# sche_DPN_ControlLed.net
KiCad netlist of a schematic drawn in Altium Designer
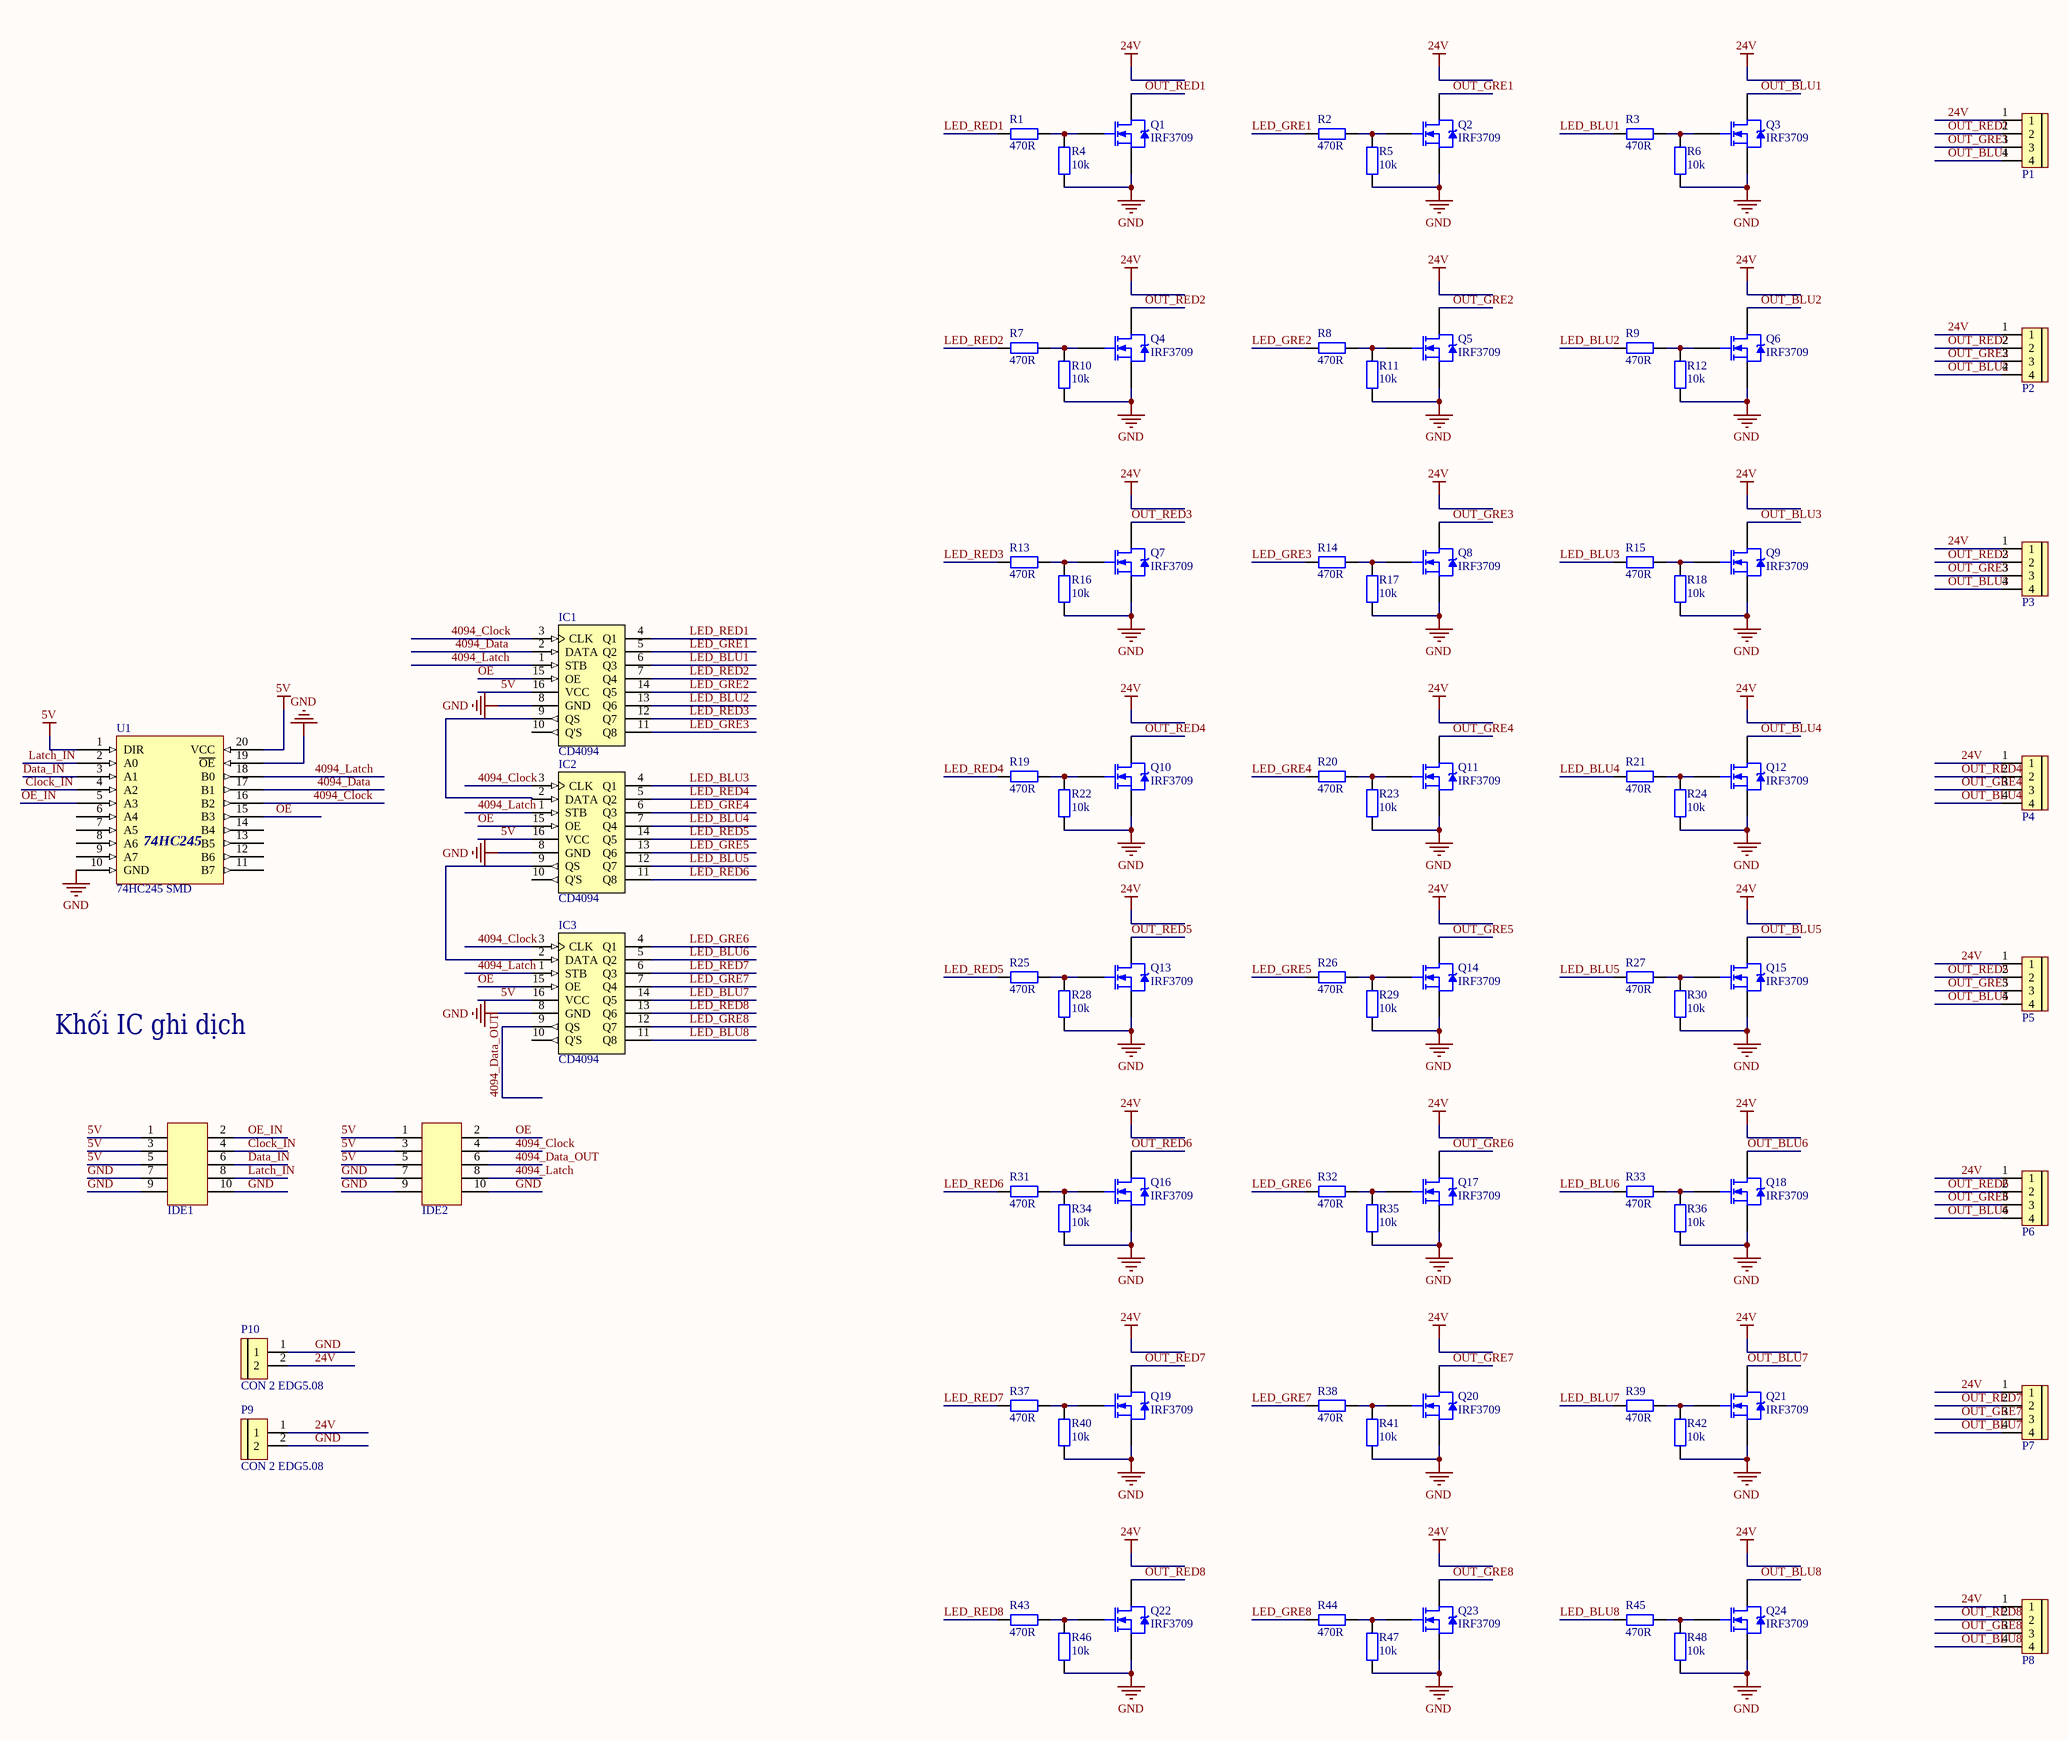
[diagram p0: sche_DPN_ControlLed.SchDoc]

(export (version "E")
  (design (tool "Eeschema 10.0.6"))
  (components
    (comp (ref "IC1")
      (value "CD4094")
      (footprint "CD4094")
      (description "Dán")
      (libsource (lib "IC") (part "CD4094 SMD"))
    )
    (comp (ref "IC2")
      (value "CD4094")
      (footprint "CD4094")
      (description "Dán")
      (libsource (lib "IC") (part "CD4094 SMD"))
    )
    (comp (ref "IC3")
      (value "CD4094")
      (footprint "CD4094")
      (description "Dán")
      (libsource (lib "IC") (part "CD4094 SMD"))
    )
    (comp (ref "IDE1")
      (value "IDE10")
      (footprint "IDE10_Cong")
      (libsource (lib "Component") (part "IDE 10 DT"))
    )
    (comp (ref "IDE2")
      (value "IDE10")
      (footprint "IDE10_Cong")
      (libsource (lib "Component") (part "IDE 10 DT"))
    )
    (comp (ref "P1")
      (value "CON 4 EDG5.08")
      (footprint "CON 4 4EDG5.08")
      (description "Cắm")
      (libsource (lib "Connector") (part "CON 4 EDG5.08"))
    )
    (comp (ref "P2")
      (value "CON 4 EDG5.08")
      (footprint "CON 4 4EDG5.08")
      (description "Cắm")
      (libsource (lib "Connector") (part "CON 4 EDG5.08"))
    )
    (comp (ref "P3")
      (value "CON 4 EDG5.08")
      (footprint "CON 4 4EDG5.08")
      (description "Cắm")
      (libsource (lib "Connector") (part "CON 4 EDG5.08"))
    )
    (comp (ref "P4")
      (value "CON 4 EDG5.08")
      (footprint "CON 4 4EDG5.08")
      (description "Cắm")
      (libsource (lib "Connector") (part "CON 4 EDG5.08"))
    )
    (comp (ref "P5")
      (value "CON 4 EDG5.08")
      (footprint "CON 4 4EDG5.08")
      (description "Cắm")
      (libsource (lib "Connector") (part "CON 4 EDG5.08"))
    )
    (comp (ref "P6")
      (value "CON 4 EDG5.08")
      (footprint "CON 4 4EDG5.08")
      (description "Cắm")
      (libsource (lib "Connector") (part "CON 4 EDG5.08"))
    )
    (comp (ref "P7")
      (value "CON 4 EDG5.08")
      (footprint "CON 4 4EDG5.08")
      (description "Cắm")
      (libsource (lib "Connector") (part "CON 4 EDG5.08"))
    )
    (comp (ref "P8")
      (value "CON 4 EDG5.08")
      (footprint "CON 4 4EDG5.08")
      (description "Cắm")
      (libsource (lib "Connector") (part "CON 4 EDG5.08"))
    )
    (comp (ref "P9")
      (value "CON 2 EDG5.08")
      (footprint "CON 2 2EDG5.08")
      (description "Cắm")
      (libsource (lib "Connector") (part "CON 2 EDG5.08"))
    )
    (comp (ref "P10")
      (value "CON 2 EDG5.08")
      (footprint "CON 2 2EDG5.08")
      (description "Cắm")
      (libsource (lib "Connector") (part "CON 2 EDG5.08"))
    )
    (comp (ref "Q1")
      (value "IRF3709")
      (footprint "D2PAK")
      (description "N-Channel Power MOSFET")
      (libsource (lib "TranFet") (part "IRF3709S SMD"))
    )
    (comp (ref "Q2")
      (value "IRF3709")
      (footprint "D2PAK")
      (description "N-Channel Power MOSFET")
      (libsource (lib "TranFet") (part "IRF3709S SMD"))
    )
    (comp (ref "Q3")
      (value "IRF3709")
      (footprint "D2PAK")
      (description "N-Channel Power MOSFET")
      (libsource (lib "TranFet") (part "IRF3709S SMD"))
    )
    (comp (ref "Q4")
      (value "IRF3709")
      (footprint "D2PAK")
      (description "N-Channel Power MOSFET")
      (libsource (lib "TranFet") (part "IRF3709S SMD"))
    )
    (comp (ref "Q5")
      (value "IRF3709")
      (footprint "D2PAK")
      (description "N-Channel Power MOSFET")
      (libsource (lib "TranFet") (part "IRF3709S SMD"))
    )
    (comp (ref "Q6")
      (value "IRF3709")
      (footprint "D2PAK")
      (description "N-Channel Power MOSFET")
      (libsource (lib "TranFet") (part "IRF3709S SMD"))
    )
    (comp (ref "Q7")
      (value "IRF3709")
      (footprint "D2PAK")
      (description "N-Channel Power MOSFET")
      (libsource (lib "TranFet") (part "IRF3709S SMD"))
    )
    (comp (ref "Q8")
      (value "IRF3709")
      (footprint "D2PAK")
      (description "N-Channel Power MOSFET")
      (libsource (lib "TranFet") (part "IRF3709S SMD"))
    )
    (comp (ref "Q9")
      (value "IRF3709")
      (footprint "D2PAK")
      (description "N-Channel Power MOSFET")
      (libsource (lib "TranFet") (part "IRF3709S SMD"))
    )
    (comp (ref "Q10")
      (value "IRF3709")
      (footprint "D2PAK")
      (description "N-Channel Power MOSFET")
      (libsource (lib "TranFet") (part "IRF3709S SMD"))
    )
    (comp (ref "Q11")
      (value "IRF3709")
      (footprint "D2PAK")
      (description "N-Channel Power MOSFET")
      (libsource (lib "TranFet") (part "IRF3709S SMD"))
    )
    (comp (ref "Q12")
      (value "IRF3709")
      (footprint "D2PAK")
      (description "N-Channel Power MOSFET")
      (libsource (lib "TranFet") (part "IRF3709S SMD"))
    )
    (comp (ref "Q13")
      (value "IRF3709")
      (footprint "D2PAK")
      (description "N-Channel Power MOSFET")
      (libsource (lib "TranFet") (part "IRF3709S SMD"))
    )
    (comp (ref "Q14")
      (value "IRF3709")
      (footprint "D2PAK")
      (description "N-Channel Power MOSFET")
      (libsource (lib "TranFet") (part "IRF3709S SMD"))
    )
    (comp (ref "Q15")
      (value "IRF3709")
      (footprint "D2PAK")
      (description "N-Channel Power MOSFET")
      (libsource (lib "TranFet") (part "IRF3709S SMD"))
    )
    (comp (ref "Q16")
      (value "IRF3709")
      (footprint "D2PAK")
      (description "N-Channel Power MOSFET")
      (libsource (lib "TranFet") (part "IRF3709S SMD"))
    )
    (comp (ref "Q17")
      (value "IRF3709")
      (footprint "D2PAK")
      (description "N-Channel Power MOSFET")
      (libsource (lib "TranFet") (part "IRF3709S SMD"))
    )
    (comp (ref "Q18")
      (value "IRF3709")
      (footprint "D2PAK")
      (description "N-Channel Power MOSFET")
      (libsource (lib "TranFet") (part "IRF3709S SMD"))
    )
    (comp (ref "Q19")
      (value "IRF3709")
      (footprint "D2PAK")
      (description "N-Channel Power MOSFET")
      (libsource (lib "TranFet") (part "IRF3709S SMD"))
    )
    (comp (ref "Q20")
      (value "IRF3709")
      (footprint "D2PAK")
      (description "N-Channel Power MOSFET")
      (libsource (lib "TranFet") (part "IRF3709S SMD"))
    )
    (comp (ref "Q21")
      (value "IRF3709")
      (footprint "D2PAK")
      (description "N-Channel Power MOSFET")
      (libsource (lib "TranFet") (part "IRF3709S SMD"))
    )
    (comp (ref "Q22")
      (value "IRF3709")
      (footprint "D2PAK")
      (description "N-Channel Power MOSFET")
      (libsource (lib "TranFet") (part "IRF3709S SMD"))
    )
    (comp (ref "Q23")
      (value "IRF3709")
      (footprint "D2PAK")
      (description "N-Channel Power MOSFET")
      (libsource (lib "TranFet") (part "IRF3709S SMD"))
    )
    (comp (ref "Q24")
      (value "IRF3709")
      (footprint "D2PAK")
      (description "N-Channel Power MOSFET")
      (libsource (lib "TranFet") (part "IRF3709S SMD"))
    )
    (comp (ref "R1")
      (value "470R")
      (footprint "Tro SMD 0805")
      (description "Dán")
      (libsource (lib "Dien Tro") (part "Tro 0805 5% 470R"))
    )
    (comp (ref "R2")
      (value "470R")
      (footprint "Tro SMD 0805")
      (description "Dán")
      (libsource (lib "Dien Tro") (part "Tro 0805 5% 470R"))
    )
    (comp (ref "R3")
      (value "470R")
      (footprint "Tro SMD 0805")
      (description "Dán")
      (libsource (lib "Dien Tro") (part "Tro 0805 5% 470R"))
    )
    (comp (ref "R4")
      (value "10k")
      (footprint "tro smd 0805")
      (description "Dán")
      (libsource (lib "Dien Tro") (part "Tro 0805 5% 10k"))
    )
    (comp (ref "R5")
      (value "10k")
      (footprint "tro smd 0805")
      (description "Dán")
      (libsource (lib "Dien Tro") (part "Tro 0805 5% 10k"))
    )
    (comp (ref "R6")
      (value "10k")
      (footprint "tro smd 0805")
      (description "Dán")
      (libsource (lib "Dien Tro") (part "Tro 0805 5% 10k"))
    )
    (comp (ref "R7")
      (value "470R")
      (footprint "Tro SMD 0805")
      (description "Dán")
      (libsource (lib "Dien Tro") (part "Tro 0805 5% 470R"))
    )
    (comp (ref "R8")
      (value "470R")
      (footprint "Tro SMD 0805")
      (description "Dán")
      (libsource (lib "Dien Tro") (part "Tro 0805 5% 470R"))
    )
    (comp (ref "R9")
      (value "470R")
      (footprint "Tro SMD 0805")
      (description "Dán")
      (libsource (lib "Dien Tro") (part "Tro 0805 5% 470R"))
    )
    (comp (ref "R10")
      (value "10k")
      (footprint "tro smd 0805")
      (description "Dán")
      (libsource (lib "Dien Tro") (part "Tro 0805 5% 10k"))
    )
    (comp (ref "R11")
      (value "10k")
      (footprint "tro smd 0805")
      (description "Dán")
      (libsource (lib "Dien Tro") (part "Tro 0805 5% 10k"))
    )
    (comp (ref "R12")
      (value "10k")
      (footprint "tro smd 0805")
      (description "Dán")
      (libsource (lib "Dien Tro") (part "Tro 0805 5% 10k"))
    )
    (comp (ref "R13")
      (value "470R")
      (footprint "Tro SMD 0805")
      (description "Dán")
      (libsource (lib "Dien Tro") (part "Tro 0805 5% 470R"))
    )
    (comp (ref "R14")
      (value "470R")
      (footprint "Tro SMD 0805")
      (description "Dán")
      (libsource (lib "Dien Tro") (part "Tro 0805 5% 470R"))
    )
    (comp (ref "R15")
      (value "470R")
      (footprint "Tro SMD 0805")
      (description "Dán")
      (libsource (lib "Dien Tro") (part "Tro 0805 5% 470R"))
    )
    (comp (ref "R16")
      (value "10k")
      (footprint "tro smd 0805")
      (description "Dán")
      (libsource (lib "Dien Tro") (part "Tro 0805 5% 10k"))
    )
    (comp (ref "R17")
      (value "10k")
      (footprint "tro smd 0805")
      (description "Dán")
      (libsource (lib "Dien Tro") (part "Tro 0805 5% 10k"))
    )
    (comp (ref "R18")
      (value "10k")
      (footprint "tro smd 0805")
      (description "Dán")
      (libsource (lib "Dien Tro") (part "Tro 0805 5% 10k"))
    )
    (comp (ref "R19")
      (value "470R")
      (footprint "Tro SMD 0805")
      (description "Dán")
      (libsource (lib "Dien Tro") (part "Tro 0805 5% 470R"))
    )
    (comp (ref "R20")
      (value "470R")
      (footprint "Tro SMD 0805")
      (description "Dán")
      (libsource (lib "Dien Tro") (part "Tro 0805 5% 470R"))
    )
    (comp (ref "R21")
      (value "470R")
      (footprint "Tro SMD 0805")
      (description "Dán")
      (libsource (lib "Dien Tro") (part "Tro 0805 5% 470R"))
    )
    (comp (ref "R22")
      (value "10k")
      (footprint "tro smd 0805")
      (description "Dán")
      (libsource (lib "Dien Tro") (part "Tro 0805 5% 10k"))
    )
    (comp (ref "R23")
      (value "10k")
      (footprint "tro smd 0805")
      (description "Dán")
      (libsource (lib "Dien Tro") (part "Tro 0805 5% 10k"))
    )
    (comp (ref "R24")
      (value "10k")
      (footprint "tro smd 0805")
      (description "Dán")
      (libsource (lib "Dien Tro") (part "Tro 0805 5% 10k"))
    )
    (comp (ref "R25")
      (value "470R")
      (footprint "Tro SMD 0805")
      (description "Dán")
      (libsource (lib "Dien Tro") (part "Tro 0805 5% 470R"))
    )
    (comp (ref "R26")
      (value "470R")
      (footprint "Tro SMD 0805")
      (description "Dán")
      (libsource (lib "Dien Tro") (part "Tro 0805 5% 470R"))
    )
    (comp (ref "R27")
      (value "470R")
      (footprint "Tro SMD 0805")
      (description "Dán")
      (libsource (lib "Dien Tro") (part "Tro 0805 5% 470R"))
    )
    (comp (ref "R28")
      (value "10k")
      (footprint "tro smd 0805")
      (description "Dán")
      (libsource (lib "Dien Tro") (part "Tro 0805 5% 10k"))
    )
    (comp (ref "R29")
      (value "10k")
      (footprint "tro smd 0805")
      (description "Dán")
      (libsource (lib "Dien Tro") (part "Tro 0805 5% 10k"))
    )
    (comp (ref "R30")
      (value "10k")
      (footprint "tro smd 0805")
      (description "Dán")
      (libsource (lib "Dien Tro") (part "Tro 0805 5% 10k"))
    )
    (comp (ref "R31")
      (value "470R")
      (footprint "Tro SMD 0805")
      (description "Dán")
      (libsource (lib "Dien Tro") (part "Tro 0805 5% 470R"))
    )
    (comp (ref "R32")
      (value "470R")
      (footprint "Tro SMD 0805")
      (description "Dán")
      (libsource (lib "Dien Tro") (part "Tro 0805 5% 470R"))
    )
    (comp (ref "R33")
      (value "470R")
      (footprint "Tro SMD 0805")
      (description "Dán")
      (libsource (lib "Dien Tro") (part "Tro 0805 5% 470R"))
    )
    (comp (ref "R34")
      (value "10k")
      (footprint "tro smd 0805")
      (description "Dán")
      (libsource (lib "Dien Tro") (part "Tro 0805 5% 10k"))
    )
    (comp (ref "R35")
      (value "10k")
      (footprint "tro smd 0805")
      (description "Dán")
      (libsource (lib "Dien Tro") (part "Tro 0805 5% 10k"))
    )
    (comp (ref "R36")
      (value "10k")
      (footprint "tro smd 0805")
      (description "Dán")
      (libsource (lib "Dien Tro") (part "Tro 0805 5% 10k"))
    )
    (comp (ref "R37")
      (value "470R")
      (footprint "Tro SMD 0805")
      (description "Dán")
      (libsource (lib "Dien Tro") (part "Tro 0805 5% 470R"))
    )
    (comp (ref "R38")
      (value "470R")
      (footprint "Tro SMD 0805")
      (description "Dán")
      (libsource (lib "Dien Tro") (part "Tro 0805 5% 470R"))
    )
    (comp (ref "R39")
      (value "470R")
      (footprint "Tro SMD 0805")
      (description "Dán")
      (libsource (lib "Dien Tro") (part "Tro 0805 5% 470R"))
    )
    (comp (ref "R40")
      (value "10k")
      (footprint "tro smd 0805")
      (description "Dán")
      (libsource (lib "Dien Tro") (part "Tro 0805 5% 10k"))
    )
    (comp (ref "R41")
      (value "10k")
      (footprint "tro smd 0805")
      (description "Dán")
      (libsource (lib "Dien Tro") (part "Tro 0805 5% 10k"))
    )
    (comp (ref "R42")
      (value "10k")
      (footprint "tro smd 0805")
      (description "Dán")
      (libsource (lib "Dien Tro") (part "Tro 0805 5% 10k"))
    )
    (comp (ref "R43")
      (value "470R")
      (footprint "Tro SMD 0805")
      (description "Dán")
      (libsource (lib "Dien Tro") (part "Tro 0805 5% 470R"))
    )
    (comp (ref "R44")
      (value "470R")
      (footprint "Tro SMD 0805")
      (description "Dán")
      (libsource (lib "Dien Tro") (part "Tro 0805 5% 470R"))
    )
    (comp (ref "R45")
      (value "470R")
      (footprint "Tro SMD 0805")
      (description "Dán")
      (libsource (lib "Dien Tro") (part "Tro 0805 5% 470R"))
    )
    (comp (ref "R46")
      (value "10k")
      (footprint "tro smd 0805")
      (description "Dán")
      (libsource (lib "Dien Tro") (part "Tro 0805 5% 10k"))
    )
    (comp (ref "R47")
      (value "10k")
      (footprint "tro smd 0805")
      (description "Dán")
      (libsource (lib "Dien Tro") (part "Tro 0805 5% 10k"))
    )
    (comp (ref "R48")
      (value "10k")
      (footprint "tro smd 0805")
      (description "Dán")
      (libsource (lib "Dien Tro") (part "Tro 0805 5% 10k"))
    )
    (comp (ref "U1")
      (value "74HC245 SMD")
      (footprint "SOP 20")
      (description "Dán")
      (libsource (lib "IC") (part "74HC245 SMD"))
    )
  )
  (nets
    (net (code "1") (name "/4094_Clock") (class "Default")
      (node (ref "IC1") (pin "3") (pinfunction "CLK_3") (pintype "input"))
      (node (ref "IC2") (pin "3") (pinfunction "CLK_3") (pintype "input"))
      (node (ref "IC3") (pin "3") (pinfunction "CLK_3") (pintype "input"))
      (node (ref "IDE2") (pin "4") (pinfunction "4_4") (pintype "passive"))
      (node (ref "U1") (pin "16") (pinfunction "B2_16") (pintype "output"))
    )
    (net (code "2") (name "/4094_Data") (class "Default")
      (node (ref "IC1") (pin "2") (pinfunction "DATA_2") (pintype "input"))
      (node (ref "U1") (pin "17") (pinfunction "B1_17") (pintype "output"))
    )
    (net (code "3") (name "/4094_Data_OUT") (class "Default")
      (node (ref "IC3") (pin "9") (pinfunction "QS_9") (pintype "output"))
      (node (ref "IDE2") (pin "6") (pinfunction "6_6") (pintype "passive"))
    )
    (net (code "4") (name "/4094_Latch") (class "Default")
      (node (ref "IC1") (pin "1") (pinfunction "STB_1") (pintype "input"))
      (node (ref "IC2") (pin "1") (pinfunction "STB_1") (pintype "input"))
      (node (ref "IC3") (pin "1") (pinfunction "STB_1") (pintype "input"))
      (node (ref "IDE2") (pin "8") (pinfunction "8_8") (pintype "passive"))
      (node (ref "U1") (pin "18") (pinfunction "B0_18") (pintype "output"))
    )
    (net (code "5") (name "/Clock_IN") (class "Default")
      (node (ref "IDE1") (pin "4") (pinfunction "4_4") (pintype "passive"))
      (node (ref "U1") (pin "4") (pinfunction "A2_4") (pintype "input"))
    )
    (net (code "6") (name "/Data_IN") (class "Default")
      (node (ref "IDE1") (pin "6") (pinfunction "6_6") (pintype "passive"))
      (node (ref "U1") (pin "3") (pinfunction "A1_3") (pintype "input"))
    )
    (net (code "7") (name "/LED_BLU1") (class "Default")
      (node (ref "IC1") (pin "6") (pinfunction "Q3_6") (pintype "tri_state"))
      (node (ref "R3") (pin "1") (pinfunction "1_1") (pintype "passive"))
    )
    (net (code "8") (name "/LED_BLU2") (class "Default")
      (node (ref "IC1") (pin "13") (pinfunction "Q6_13") (pintype "tri_state"))
      (node (ref "R9") (pin "1") (pinfunction "1_1") (pintype "passive"))
    )
    (net (code "9") (name "/LED_BLU3") (class "Default")
      (node (ref "IC2") (pin "4") (pinfunction "Q1_4") (pintype "tri_state"))
      (node (ref "R15") (pin "1") (pinfunction "1_1") (pintype "passive"))
    )
    (net (code "10") (name "/LED_BLU4") (class "Default")
      (node (ref "IC2") (pin "7") (pinfunction "Q4_7") (pintype "tri_state"))
      (node (ref "R21") (pin "1") (pinfunction "1_1") (pintype "passive"))
    )
    (net (code "11") (name "/LED_BLU5") (class "Default")
      (node (ref "IC2") (pin "12") (pinfunction "Q7_12") (pintype "tri_state"))
      (node (ref "R27") (pin "1") (pinfunction "1_1") (pintype "passive"))
    )
    (net (code "12") (name "/LED_BLU6") (class "Default")
      (node (ref "IC3") (pin "5") (pinfunction "Q2_5") (pintype "tri_state"))
      (node (ref "R33") (pin "1") (pinfunction "1_1") (pintype "passive"))
    )
    (net (code "13") (name "/LED_BLU7") (class "Default")
      (node (ref "IC3") (pin "14") (pinfunction "Q5_14") (pintype "tri_state"))
      (node (ref "R39") (pin "1") (pinfunction "1_1") (pintype "passive"))
    )
    (net (code "14") (name "/LED_BLU8") (class "Default")
      (node (ref "IC3") (pin "11") (pinfunction "Q8_11") (pintype "tri_state"))
      (node (ref "R45") (pin "1") (pinfunction "1_1") (pintype "passive"))
    )
    (net (code "15") (name "/LED_GRE1") (class "Default")
      (node (ref "IC1") (pin "5") (pinfunction "Q2_5") (pintype "tri_state"))
      (node (ref "R2") (pin "1") (pinfunction "1_1") (pintype "passive"))
    )
    (net (code "16") (name "/LED_GRE2") (class "Default")
      (node (ref "IC1") (pin "14") (pinfunction "Q5_14") (pintype "tri_state"))
      (node (ref "R8") (pin "1") (pinfunction "1_1") (pintype "passive"))
    )
    (net (code "17") (name "/LED_GRE3") (class "Default")
      (node (ref "IC1") (pin "11") (pinfunction "Q8_11") (pintype "tri_state"))
      (node (ref "R14") (pin "1") (pinfunction "1_1") (pintype "passive"))
    )
    (net (code "18") (name "/LED_GRE4") (class "Default")
      (node (ref "IC2") (pin "6") (pinfunction "Q3_6") (pintype "tri_state"))
      (node (ref "R20") (pin "1") (pinfunction "1_1") (pintype "passive"))
    )
    (net (code "19") (name "/LED_GRE5") (class "Default")
      (node (ref "IC2") (pin "13") (pinfunction "Q6_13") (pintype "tri_state"))
      (node (ref "R26") (pin "1") (pinfunction "1_1") (pintype "passive"))
    )
    (net (code "20") (name "/LED_GRE6") (class "Default")
      (node (ref "IC3") (pin "4") (pinfunction "Q1_4") (pintype "tri_state"))
      (node (ref "R32") (pin "1") (pinfunction "1_1") (pintype "passive"))
    )
    (net (code "21") (name "/LED_GRE7") (class "Default")
      (node (ref "IC3") (pin "7") (pinfunction "Q4_7") (pintype "tri_state"))
      (node (ref "R38") (pin "1") (pinfunction "1_1") (pintype "passive"))
    )
    (net (code "22") (name "/LED_GRE8") (class "Default")
      (node (ref "IC3") (pin "12") (pinfunction "Q7_12") (pintype "tri_state"))
      (node (ref "R44") (pin "1") (pinfunction "1_1") (pintype "passive"))
    )
    (net (code "23") (name "/LED_RED1") (class "Default")
      (node (ref "IC1") (pin "4") (pinfunction "Q1_4") (pintype "tri_state"))
      (node (ref "R1") (pin "1") (pinfunction "1_1") (pintype "passive"))
    )
    (net (code "24") (name "/LED_RED2") (class "Default")
      (node (ref "IC1") (pin "7") (pinfunction "Q4_7") (pintype "tri_state"))
      (node (ref "R7") (pin "1") (pinfunction "1_1") (pintype "passive"))
    )
    (net (code "25") (name "/LED_RED3") (class "Default")
      (node (ref "IC1") (pin "12") (pinfunction "Q7_12") (pintype "tri_state"))
      (node (ref "R13") (pin "1") (pinfunction "1_1") (pintype "passive"))
    )
    (net (code "26") (name "/LED_RED4") (class "Default")
      (node (ref "IC2") (pin "5") (pinfunction "Q2_5") (pintype "tri_state"))
      (node (ref "R19") (pin "1") (pinfunction "1_1") (pintype "passive"))
    )
    (net (code "27") (name "/LED_RED5") (class "Default")
      (node (ref "IC2") (pin "14") (pinfunction "Q5_14") (pintype "tri_state"))
      (node (ref "R25") (pin "1") (pinfunction "1_1") (pintype "passive"))
    )
    (net (code "28") (name "/LED_RED6") (class "Default")
      (node (ref "IC2") (pin "11") (pinfunction "Q8_11") (pintype "tri_state"))
      (node (ref "R31") (pin "1") (pinfunction "1_1") (pintype "passive"))
    )
    (net (code "29") (name "/LED_RED7") (class "Default")
      (node (ref "IC3") (pin "6") (pinfunction "Q3_6") (pintype "tri_state"))
      (node (ref "R37") (pin "1") (pinfunction "1_1") (pintype "passive"))
    )
    (net (code "30") (name "/LED_RED8") (class "Default")
      (node (ref "IC3") (pin "13") (pinfunction "Q6_13") (pintype "tri_state"))
      (node (ref "R43") (pin "1") (pinfunction "1_1") (pintype "passive"))
    )
    (net (code "31") (name "/Latch_IN") (class "Default")
      (node (ref "IDE1") (pin "8") (pinfunction "8_8") (pintype "passive"))
      (node (ref "U1") (pin "2") (pinfunction "A0_2") (pintype "input"))
    )
    (net (code "32") (name "/OE") (class "Default")
      (node (ref "IC1") (pin "15") (pinfunction "OE_15") (pintype "input"))
      (node (ref "IC2") (pin "15") (pinfunction "OE_15") (pintype "input"))
      (node (ref "IC3") (pin "15") (pinfunction "OE_15") (pintype "input"))
      (node (ref "IDE2") (pin "2") (pinfunction "2_2") (pintype "passive"))
      (node (ref "U1") (pin "15") (pinfunction "B3_15") (pintype "output"))
    )
    (net (code "33") (name "/OE_IN") (class "Default")
      (node (ref "IDE1") (pin "2") (pinfunction "2_2") (pintype "passive"))
      (node (ref "U1") (pin "5") (pinfunction "A3_5") (pintype "input"))
    )
    (net (code "34") (name "/OUT_BLU1") (class "Default")
      (node (ref "P1") (pin "4") (pinfunction "4_4") (pintype "passive"))
      (node (ref "Q3") (pin "2") (pinfunction "D_2") (pintype "passive"))
    )
    (net (code "35") (name "/OUT_BLU2") (class "Default")
      (node (ref "P2") (pin "4") (pinfunction "4_4") (pintype "passive"))
      (node (ref "Q6") (pin "2") (pinfunction "D_2") (pintype "passive"))
    )
    (net (code "36") (name "/OUT_BLU3") (class "Default")
      (node (ref "P3") (pin "4") (pinfunction "4_4") (pintype "passive"))
      (node (ref "Q9") (pin "2") (pinfunction "D_2") (pintype "passive"))
    )
    (net (code "37") (name "/OUT_BLU4") (class "Default")
      (node (ref "P4") (pin "4") (pinfunction "4_4") (pintype "passive"))
      (node (ref "Q12") (pin "2") (pinfunction "D_2") (pintype "passive"))
    )
    (net (code "38") (name "/OUT_BLU5") (class "Default")
      (node (ref "P5") (pin "4") (pinfunction "4_4") (pintype "passive"))
      (node (ref "Q15") (pin "2") (pinfunction "D_2") (pintype "passive"))
    )
    (net (code "39") (name "/OUT_BLU6") (class "Default")
      (node (ref "P6") (pin "4") (pinfunction "4_4") (pintype "passive"))
      (node (ref "Q18") (pin "2") (pinfunction "D_2") (pintype "passive"))
    )
    (net (code "40") (name "/OUT_BLU7") (class "Default")
      (node (ref "P7") (pin "4") (pinfunction "4_4") (pintype "passive"))
      (node (ref "Q21") (pin "2") (pinfunction "D_2") (pintype "passive"))
    )
    (net (code "41") (name "/OUT_BLU8") (class "Default")
      (node (ref "P8") (pin "4") (pinfunction "4_4") (pintype "passive"))
      (node (ref "Q24") (pin "2") (pinfunction "D_2") (pintype "passive"))
    )
    (net (code "42") (name "/OUT_GRE1") (class "Default")
      (node (ref "P1") (pin "3") (pinfunction "3_3") (pintype "passive"))
      (node (ref "Q2") (pin "2") (pinfunction "D_2") (pintype "passive"))
    )
    (net (code "43") (name "/OUT_GRE2") (class "Default")
      (node (ref "P2") (pin "3") (pinfunction "3_3") (pintype "passive"))
      (node (ref "Q5") (pin "2") (pinfunction "D_2") (pintype "passive"))
    )
    (net (code "44") (name "/OUT_GRE3") (class "Default")
      (node (ref "P3") (pin "3") (pinfunction "3_3") (pintype "passive"))
      (node (ref "Q8") (pin "2") (pinfunction "D_2") (pintype "passive"))
    )
    (net (code "45") (name "/OUT_GRE4") (class "Default")
      (node (ref "P4") (pin "3") (pinfunction "3_3") (pintype "passive"))
      (node (ref "Q11") (pin "2") (pinfunction "D_2") (pintype "passive"))
    )
    (net (code "46") (name "/OUT_GRE5") (class "Default")
      (node (ref "P5") (pin "3") (pinfunction "3_3") (pintype "passive"))
      (node (ref "Q14") (pin "2") (pinfunction "D_2") (pintype "passive"))
    )
    (net (code "47") (name "/OUT_GRE6") (class "Default")
      (node (ref "P6") (pin "3") (pinfunction "3_3") (pintype "passive"))
      (node (ref "Q17") (pin "2") (pinfunction "D_2") (pintype "passive"))
    )
    (net (code "48") (name "/OUT_GRE7") (class "Default")
      (node (ref "P7") (pin "3") (pinfunction "3_3") (pintype "passive"))
      (node (ref "Q20") (pin "2") (pinfunction "D_2") (pintype "passive"))
    )
    (net (code "49") (name "/OUT_GRE8") (class "Default")
      (node (ref "P8") (pin "3") (pinfunction "3_3") (pintype "passive"))
      (node (ref "Q23") (pin "2") (pinfunction "D_2") (pintype "passive"))
    )
    (net (code "50") (name "/OUT_RED1") (class "Default")
      (node (ref "P1") (pin "2") (pinfunction "2_2") (pintype "passive"))
      (node (ref "Q1") (pin "2") (pinfunction "D_2") (pintype "passive"))
    )
    (net (code "51") (name "/OUT_RED2") (class "Default")
      (node (ref "P2") (pin "2") (pinfunction "2_2") (pintype "passive"))
      (node (ref "Q4") (pin "2") (pinfunction "D_2") (pintype "passive"))
    )
    (net (code "52") (name "/OUT_RED3") (class "Default")
      (node (ref "P3") (pin "2") (pinfunction "2_2") (pintype "passive"))
      (node (ref "Q7") (pin "2") (pinfunction "D_2") (pintype "passive"))
    )
    (net (code "53") (name "/OUT_RED4") (class "Default")
      (node (ref "P4") (pin "2") (pinfunction "2_2") (pintype "passive"))
      (node (ref "Q10") (pin "2") (pinfunction "D_2") (pintype "passive"))
    )
    (net (code "54") (name "/OUT_RED5") (class "Default")
      (node (ref "P5") (pin "2") (pinfunction "2_2") (pintype "passive"))
      (node (ref "Q13") (pin "2") (pinfunction "D_2") (pintype "passive"))
    )
    (net (code "55") (name "/OUT_RED6") (class "Default")
      (node (ref "P6") (pin "2") (pinfunction "2_2") (pintype "passive"))
      (node (ref "Q16") (pin "2") (pinfunction "D_2") (pintype "passive"))
    )
    (net (code "56") (name "/OUT_RED7") (class "Default")
      (node (ref "P7") (pin "2") (pinfunction "2_2") (pintype "passive"))
      (node (ref "Q19") (pin "2") (pinfunction "D_2") (pintype "passive"))
    )
    (net (code "57") (name "/OUT_RED8") (class "Default")
      (node (ref "P8") (pin "2") (pinfunction "2_2") (pintype "passive"))
      (node (ref "Q22") (pin "2") (pinfunction "D_2") (pintype "passive"))
    )
    (net (code "58") (name "5V") (class "Default")
      (node (ref "IC1") (pin "16") (pinfunction "VCC_16") (pintype "power_in"))
      (node (ref "IC2") (pin "16") (pinfunction "VCC_16") (pintype "power_in"))
      (node (ref "IC3") (pin "16") (pinfunction "VCC_16") (pintype "power_in"))
      (node (ref "IDE1") (pin "1") (pinfunction "1_1") (pintype "passive"))
      (node (ref "IDE1") (pin "3") (pinfunction "3_3") (pintype "passive"))
      (node (ref "IDE1") (pin "5") (pinfunction "5_5") (pintype "passive"))
      (node (ref "IDE2") (pin "1") (pinfunction "1_1") (pintype "passive"))
      (node (ref "IDE2") (pin "3") (pinfunction "3_3") (pintype "passive"))
      (node (ref "IDE2") (pin "5") (pinfunction "5_5") (pintype "passive"))
      (node (ref "U1") (pin "1") (pinfunction "DIR_1") (pintype "input"))
      (node (ref "U1") (pin "20") (pinfunction "VCC_20") (pintype "input"))
    )
    (net (code "59") (name "24V") (class "Default")
      (node (ref "P1") (pin "1") (pinfunction "1_1") (pintype "passive"))
      (node (ref "P10") (pin "2") (pinfunction "2_2") (pintype "passive"))
      (node (ref "P2") (pin "1") (pinfunction "1_1") (pintype "passive"))
      (node (ref "P3") (pin "1") (pinfunction "1_1") (pintype "passive"))
      (node (ref "P4") (pin "1") (pinfunction "1_1") (pintype "passive"))
      (node (ref "P5") (pin "1") (pinfunction "1_1") (pintype "passive"))
      (node (ref "P6") (pin "1") (pinfunction "1_1") (pintype "passive"))
      (node (ref "P7") (pin "1") (pinfunction "1_1") (pintype "passive"))
      (node (ref "P8") (pin "1") (pinfunction "1_1") (pintype "passive"))
      (node (ref "P9") (pin "1") (pinfunction "1_1") (pintype "passive"))
    )
    (net (code "60") (name "GND") (class "Default")
      (node (ref "IC1") (pin "8") (pinfunction "GND_8") (pintype "power_in"))
      (node (ref "IC2") (pin "8") (pinfunction "GND_8") (pintype "power_in"))
      (node (ref "IC3") (pin "8") (pinfunction "GND_8") (pintype "power_in"))
      (node (ref "IDE1") (pin "10") (pinfunction "10_10") (pintype "passive"))
      (node (ref "IDE1") (pin "7") (pinfunction "7_7") (pintype "passive"))
      (node (ref "IDE1") (pin "9") (pinfunction "9_9") (pintype "passive"))
      (node (ref "IDE2") (pin "10") (pinfunction "10_10") (pintype "passive"))
      (node (ref "IDE2") (pin "7") (pinfunction "7_7") (pintype "passive"))
      (node (ref "IDE2") (pin "9") (pinfunction "9_9") (pintype "passive"))
      (node (ref "P10") (pin "1") (pinfunction "1_1") (pintype "passive"))
      (node (ref "P9") (pin "2") (pinfunction "2_2") (pintype "passive"))
      (node (ref "Q1") (pin "3") (pinfunction "S_3") (pintype "passive"))
      (node (ref "Q10") (pin "3") (pinfunction "S_3") (pintype "passive"))
      (node (ref "Q11") (pin "3") (pinfunction "S_3") (pintype "passive"))
      (node (ref "Q12") (pin "3") (pinfunction "S_3") (pintype "passive"))
      (node (ref "Q13") (pin "3") (pinfunction "S_3") (pintype "passive"))
      (node (ref "Q14") (pin "3") (pinfunction "S_3") (pintype "passive"))
      (node (ref "Q15") (pin "3") (pinfunction "S_3") (pintype "passive"))
      (node (ref "Q16") (pin "3") (pinfunction "S_3") (pintype "passive"))
      (node (ref "Q17") (pin "3") (pinfunction "S_3") (pintype "passive"))
      (node (ref "Q18") (pin "3") (pinfunction "S_3") (pintype "passive"))
      (node (ref "Q19") (pin "3") (pinfunction "S_3") (pintype "passive"))
      (node (ref "Q2") (pin "3") (pinfunction "S_3") (pintype "passive"))
      (node (ref "Q20") (pin "3") (pinfunction "S_3") (pintype "passive"))
      (node (ref "Q21") (pin "3") (pinfunction "S_3") (pintype "passive"))
      (node (ref "Q22") (pin "3") (pinfunction "S_3") (pintype "passive"))
      (node (ref "Q23") (pin "3") (pinfunction "S_3") (pintype "passive"))
      (node (ref "Q24") (pin "3") (pinfunction "S_3") (pintype "passive"))
      (node (ref "Q3") (pin "3") (pinfunction "S_3") (pintype "passive"))
      (node (ref "Q4") (pin "3") (pinfunction "S_3") (pintype "passive"))
      (node (ref "Q5") (pin "3") (pinfunction "S_3") (pintype "passive"))
      (node (ref "Q6") (pin "3") (pinfunction "S_3") (pintype "passive"))
      (node (ref "Q7") (pin "3") (pinfunction "S_3") (pintype "passive"))
      (node (ref "Q8") (pin "3") (pinfunction "S_3") (pintype "passive"))
      (node (ref "Q9") (pin "3") (pinfunction "S_3") (pintype "passive"))
      (node (ref "R10") (pin "1") (pinfunction "1_1") (pintype "passive"))
      (node (ref "R11") (pin "1") (pinfunction "1_1") (pintype "passive"))
      (node (ref "R12") (pin "1") (pinfunction "1_1") (pintype "passive"))
      (node (ref "R16") (pin "1") (pinfunction "1_1") (pintype "passive"))
      (node (ref "R17") (pin "1") (pinfunction "1_1") (pintype "passive"))
      (node (ref "R18") (pin "1") (pinfunction "1_1") (pintype "passive"))
      (node (ref "R22") (pin "1") (pinfunction "1_1") (pintype "passive"))
      (node (ref "R23") (pin "1") (pinfunction "1_1") (pintype "passive"))
      (node (ref "R24") (pin "1") (pinfunction "1_1") (pintype "passive"))
      (node (ref "R28") (pin "1") (pinfunction "1_1") (pintype "passive"))
      (node (ref "R29") (pin "1") (pinfunction "1_1") (pintype "passive"))
      (node (ref "R30") (pin "1") (pinfunction "1_1") (pintype "passive"))
      (node (ref "R34") (pin "1") (pinfunction "1_1") (pintype "passive"))
      (node (ref "R35") (pin "1") (pinfunction "1_1") (pintype "passive"))
      (node (ref "R36") (pin "1") (pinfunction "1_1") (pintype "passive"))
      (node (ref "R4") (pin "1") (pinfunction "1_1") (pintype "passive"))
      (node (ref "R40") (pin "1") (pinfunction "1_1") (pintype "passive"))
      (node (ref "R41") (pin "1") (pinfunction "1_1") (pintype "passive"))
      (node (ref "R42") (pin "1") (pinfunction "1_1") (pintype "passive"))
      (node (ref "R46") (pin "1") (pinfunction "1_1") (pintype "passive"))
      (node (ref "R47") (pin "1") (pinfunction "1_1") (pintype "passive"))
      (node (ref "R48") (pin "1") (pinfunction "1_1") (pintype "passive"))
      (node (ref "R5") (pin "1") (pinfunction "1_1") (pintype "passive"))
      (node (ref "R6") (pin "1") (pinfunction "1_1") (pintype "passive"))
      (node (ref "U1") (pin "10") (pinfunction "GND_10") (pintype "input"))
      (node (ref "U1") (pin "19") (pinfunction "~{OE}_19") (pintype "input"))
    )
    (net (code "61") (name "Net-(IC1-QS)") (class "Default")
      (node (ref "IC1") (pin "9") (pinfunction "QS_9") (pintype "output"))
      (node (ref "IC2") (pin "2") (pinfunction "DATA_2") (pintype "input"))
    )
    (net (code "62") (name "Net-(IC2-QS)") (class "Default")
      (node (ref "IC2") (pin "9") (pinfunction "QS_9") (pintype "output"))
      (node (ref "IC3") (pin "2") (pinfunction "DATA_2") (pintype "input"))
    )
    (net (code "63") (name "Net-(Q1-G)") (class "Default")
      (node (ref "Q1") (pin "1") (pinfunction "G_1") (pintype "passive"))
      (node (ref "R1") (pin "2") (pinfunction "2_2") (pintype "passive"))
      (node (ref "R4") (pin "2") (pinfunction "2_2") (pintype "passive"))
    )
    (net (code "64") (name "Net-(Q2-G)") (class "Default")
      (node (ref "Q2") (pin "1") (pinfunction "G_1") (pintype "passive"))
      (node (ref "R2") (pin "2") (pinfunction "2_2") (pintype "passive"))
      (node (ref "R5") (pin "2") (pinfunction "2_2") (pintype "passive"))
    )
    (net (code "65") (name "Net-(Q3-G)") (class "Default")
      (node (ref "Q3") (pin "1") (pinfunction "G_1") (pintype "passive"))
      (node (ref "R3") (pin "2") (pinfunction "2_2") (pintype "passive"))
      (node (ref "R6") (pin "2") (pinfunction "2_2") (pintype "passive"))
    )
    (net (code "66") (name "Net-(Q4-G)") (class "Default")
      (node (ref "Q4") (pin "1") (pinfunction "G_1") (pintype "passive"))
      (node (ref "R10") (pin "2") (pinfunction "2_2") (pintype "passive"))
      (node (ref "R7") (pin "2") (pinfunction "2_2") (pintype "passive"))
    )
    (net (code "67") (name "Net-(Q5-G)") (class "Default")
      (node (ref "Q5") (pin "1") (pinfunction "G_1") (pintype "passive"))
      (node (ref "R11") (pin "2") (pinfunction "2_2") (pintype "passive"))
      (node (ref "R8") (pin "2") (pinfunction "2_2") (pintype "passive"))
    )
    (net (code "68") (name "Net-(Q6-G)") (class "Default")
      (node (ref "Q6") (pin "1") (pinfunction "G_1") (pintype "passive"))
      (node (ref "R12") (pin "2") (pinfunction "2_2") (pintype "passive"))
      (node (ref "R9") (pin "2") (pinfunction "2_2") (pintype "passive"))
    )
    (net (code "69") (name "Net-(Q7-G)") (class "Default")
      (node (ref "Q7") (pin "1") (pinfunction "G_1") (pintype "passive"))
      (node (ref "R13") (pin "2") (pinfunction "2_2") (pintype "passive"))
      (node (ref "R16") (pin "2") (pinfunction "2_2") (pintype "passive"))
    )
    (net (code "70") (name "Net-(Q8-G)") (class "Default")
      (node (ref "Q8") (pin "1") (pinfunction "G_1") (pintype "passive"))
      (node (ref "R14") (pin "2") (pinfunction "2_2") (pintype "passive"))
      (node (ref "R17") (pin "2") (pinfunction "2_2") (pintype "passive"))
    )
    (net (code "71") (name "Net-(Q9-G)") (class "Default")
      (node (ref "Q9") (pin "1") (pinfunction "G_1") (pintype "passive"))
      (node (ref "R15") (pin "2") (pinfunction "2_2") (pintype "passive"))
      (node (ref "R18") (pin "2") (pinfunction "2_2") (pintype "passive"))
    )
    (net (code "72") (name "Net-(Q10-G)") (class "Default")
      (node (ref "Q10") (pin "1") (pinfunction "G_1") (pintype "passive"))
      (node (ref "R19") (pin "2") (pinfunction "2_2") (pintype "passive"))
      (node (ref "R22") (pin "2") (pinfunction "2_2") (pintype "passive"))
    )
    (net (code "73") (name "Net-(Q11-G)") (class "Default")
      (node (ref "Q11") (pin "1") (pinfunction "G_1") (pintype "passive"))
      (node (ref "R20") (pin "2") (pinfunction "2_2") (pintype "passive"))
      (node (ref "R23") (pin "2") (pinfunction "2_2") (pintype "passive"))
    )
    (net (code "74") (name "Net-(Q12-G)") (class "Default")
      (node (ref "Q12") (pin "1") (pinfunction "G_1") (pintype "passive"))
      (node (ref "R21") (pin "2") (pinfunction "2_2") (pintype "passive"))
      (node (ref "R24") (pin "2") (pinfunction "2_2") (pintype "passive"))
    )
    (net (code "75") (name "Net-(Q13-G)") (class "Default")
      (node (ref "Q13") (pin "1") (pinfunction "G_1") (pintype "passive"))
      (node (ref "R25") (pin "2") (pinfunction "2_2") (pintype "passive"))
      (node (ref "R28") (pin "2") (pinfunction "2_2") (pintype "passive"))
    )
    (net (code "76") (name "Net-(Q14-G)") (class "Default")
      (node (ref "Q14") (pin "1") (pinfunction "G_1") (pintype "passive"))
      (node (ref "R26") (pin "2") (pinfunction "2_2") (pintype "passive"))
      (node (ref "R29") (pin "2") (pinfunction "2_2") (pintype "passive"))
    )
    (net (code "77") (name "Net-(Q15-G)") (class "Default")
      (node (ref "Q15") (pin "1") (pinfunction "G_1") (pintype "passive"))
      (node (ref "R27") (pin "2") (pinfunction "2_2") (pintype "passive"))
      (node (ref "R30") (pin "2") (pinfunction "2_2") (pintype "passive"))
    )
    (net (code "78") (name "Net-(Q16-G)") (class "Default")
      (node (ref "Q16") (pin "1") (pinfunction "G_1") (pintype "passive"))
      (node (ref "R31") (pin "2") (pinfunction "2_2") (pintype "passive"))
      (node (ref "R34") (pin "2") (pinfunction "2_2") (pintype "passive"))
    )
    (net (code "79") (name "Net-(Q17-G)") (class "Default")
      (node (ref "Q17") (pin "1") (pinfunction "G_1") (pintype "passive"))
      (node (ref "R32") (pin "2") (pinfunction "2_2") (pintype "passive"))
      (node (ref "R35") (pin "2") (pinfunction "2_2") (pintype "passive"))
    )
    (net (code "80") (name "Net-(Q18-G)") (class "Default")
      (node (ref "Q18") (pin "1") (pinfunction "G_1") (pintype "passive"))
      (node (ref "R33") (pin "2") (pinfunction "2_2") (pintype "passive"))
      (node (ref "R36") (pin "2") (pinfunction "2_2") (pintype "passive"))
    )
    (net (code "81") (name "Net-(Q19-G)") (class "Default")
      (node (ref "Q19") (pin "1") (pinfunction "G_1") (pintype "passive"))
      (node (ref "R37") (pin "2") (pinfunction "2_2") (pintype "passive"))
      (node (ref "R40") (pin "2") (pinfunction "2_2") (pintype "passive"))
    )
    (net (code "82") (name "Net-(Q20-G)") (class "Default")
      (node (ref "Q20") (pin "1") (pinfunction "G_1") (pintype "passive"))
      (node (ref "R38") (pin "2") (pinfunction "2_2") (pintype "passive"))
      (node (ref "R41") (pin "2") (pinfunction "2_2") (pintype "passive"))
    )
    (net (code "83") (name "Net-(Q21-G)") (class "Default")
      (node (ref "Q21") (pin "1") (pinfunction "G_1") (pintype "passive"))
      (node (ref "R39") (pin "2") (pinfunction "2_2") (pintype "passive"))
      (node (ref "R42") (pin "2") (pinfunction "2_2") (pintype "passive"))
    )
    (net (code "84") (name "Net-(Q22-G)") (class "Default")
      (node (ref "Q22") (pin "1") (pinfunction "G_1") (pintype "passive"))
      (node (ref "R43") (pin "2") (pinfunction "2_2") (pintype "passive"))
      (node (ref "R46") (pin "2") (pinfunction "2_2") (pintype "passive"))
    )
    (net (code "85") (name "Net-(Q23-G)") (class "Default")
      (node (ref "Q23") (pin "1") (pinfunction "G_1") (pintype "passive"))
      (node (ref "R44") (pin "2") (pinfunction "2_2") (pintype "passive"))
      (node (ref "R47") (pin "2") (pinfunction "2_2") (pintype "passive"))
    )
    (net (code "86") (name "Net-(Q24-G)") (class "Default")
      (node (ref "Q24") (pin "1") (pinfunction "G_1") (pintype "passive"))
      (node (ref "R45") (pin "2") (pinfunction "2_2") (pintype "passive"))
      (node (ref "R48") (pin "2") (pinfunction "2_2") (pintype "passive"))
    )
    (net (code "87") (name "unconnected-(IC1-Q'S-Pad10)") (class "Default")
      (node (ref "IC1") (pin "10") (pinfunction "Q'S_10") (pintype "output"))
    )
    (net (code "88") (name "unconnected-(IC2-Q'S-Pad10)") (class "Default")
      (node (ref "IC2") (pin "10") (pinfunction "Q'S_10") (pintype "output"))
    )
    (net (code "89") (name "unconnected-(IC3-Q'S-Pad10)") (class "Default")
      (node (ref "IC3") (pin "10") (pinfunction "Q'S_10") (pintype "output"))
    )
    (net (code "90") (name "unconnected-(U1-A4-Pad6)") (class "Default")
      (node (ref "U1") (pin "6") (pinfunction "A4_6") (pintype "input"))
    )
    (net (code "91") (name "unconnected-(U1-A5-Pad7)") (class "Default")
      (node (ref "U1") (pin "7") (pinfunction "A5_7") (pintype "input"))
    )
    (net (code "92") (name "unconnected-(U1-A6-Pad8)") (class "Default")
      (node (ref "U1") (pin "8") (pinfunction "A6_8") (pintype "input"))
    )
    (net (code "93") (name "unconnected-(U1-A7-Pad9)") (class "Default")
      (node (ref "U1") (pin "9") (pinfunction "A7_9") (pintype "input"))
    )
    (net (code "94") (name "unconnected-(U1-B4-Pad14)") (class "Default")
      (node (ref "U1") (pin "14") (pinfunction "B4_14") (pintype "output"))
    )
    (net (code "95") (name "unconnected-(U1-B5-Pad13)") (class "Default")
      (node (ref "U1") (pin "13") (pinfunction "B5_13") (pintype "output"))
    )
    (net (code "96") (name "unconnected-(U1-B6-Pad12)") (class "Default")
      (node (ref "U1") (pin "12") (pinfunction "B6_12") (pintype "output"))
    )
    (net (code "97") (name "unconnected-(U1-B7-Pad11)") (class "Default")
      (node (ref "U1") (pin "11") (pinfunction "B7_11") (pintype "output"))
    )
  )
)
